# Sheet_1_2022-06-29.net
KiCad netlist of a schematic drawn in Altium Designer
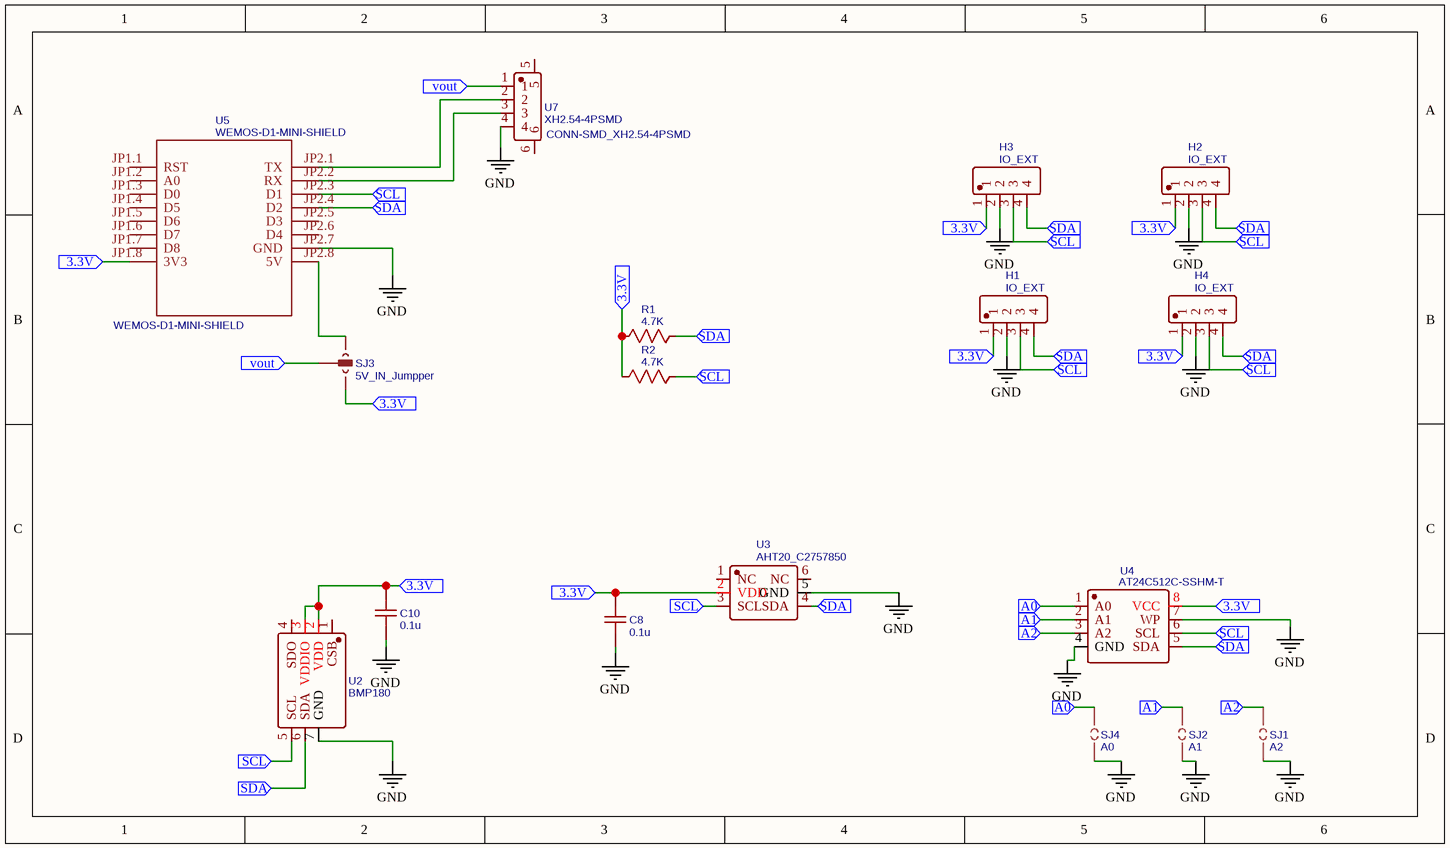
[diagram p0: Sheet_1_2022-06-29.schdoc]

(export (version "E")
  (design (tool "Eeschema 10.0.6"))
  (components
    (comp (ref "C8")
      (value "0.1u")
      (fields (field (name "CONTRIBUTOR") "LCEDA_Lib"))
      (libsource (lib "altium-import") (part "root_1_0.1u_"))
    )
    (comp (ref "C10")
      (value "0.1u")
      (fields (field (name "CONTRIBUTOR") "LCEDA_Lib"))
      (libsource (lib "altium-import") (part "root_1_0.1u_"))
    )
    (comp (ref "H1")
      (value "IO_EXT")
      (fields
        (field (name "BOM_SUPPLIER PART") "C706876")
        (field (name "BOM_MANUFACTURER PART") "X6511WV-04H-C30D60")
        (field (name "CONTRIBUTOR") "LCSC")
      )
      (libsource (lib "altium-import") (part "root_1_IO_EXT_"))
    )
    (comp (ref "H2")
      (value "IO_EXT")
      (fields
        (field (name "BOM_SUPPLIER PART") "C706876")
        (field (name "BOM_MANUFACTURER PART") "X6511WV-04H-C30D60")
        (field (name "CONTRIBUTOR") "LCSC")
      )
      (libsource (lib "altium-import") (part "root_1_IO_EXT_"))
    )
    (comp (ref "H3")
      (value "IO_EXT")
      (fields
        (field (name "BOM_SUPPLIER PART") "C706876")
        (field (name "BOM_MANUFACTURER PART") "X6511WV-04H-C30D60")
        (field (name "CONTRIBUTOR") "LCSC")
      )
      (libsource (lib "altium-import") (part "root_1_IO_EXT_"))
    )
    (comp (ref "H4")
      (value "IO_EXT")
      (fields
        (field (name "BOM_SUPPLIER PART") "C706876")
        (field (name "BOM_MANUFACTURER PART") "X6511WV-04H-C30D60")
        (field (name "CONTRIBUTOR") "LCSC")
      )
      (libsource (lib "altium-import") (part "root_1_IO_EXT_"))
    )
    (comp (ref "R1")
      (value "4.7K")
      (fields (field (name "CONTRIBUTOR") "LCEDA_Lib"))
      (libsource (lib "altium-import") (part "root_2_4.7K_"))
    )
    (comp (ref "R2")
      (value "4.7K")
      (fields (field (name "CONTRIBUTOR") "LCEDA_Lib"))
      (libsource (lib "altium-import") (part "root_2_4.7K_"))
    )
    (comp (ref "SJ1")
      (value "A2")
      (fields (field (name "CONTRIBUTOR") "torusww"))
      (libsource (lib "altium-import") (part "root_1_A2_"))
    )
    (comp (ref "SJ2")
      (value "A1")
      (fields (field (name "CONTRIBUTOR") "torusww"))
      (libsource (lib "altium-import") (part "root_1_A1_"))
    )
    (comp (ref "SJ3")
      (value "5V_IN_Jumpper")
      (fields (field (name "CONTRIBUTOR") "SparkFun"))
      (libsource (lib "altium-import") (part "root_0_5V_IN_Jumpper_"))
    )
    (comp (ref "SJ4")
      (value "A0")
      (fields (field (name "CONTRIBUTOR") "torusww"))
      (libsource (lib "altium-import") (part "root_1_A0_"))
    )
    (comp (ref "U2")
      (value "BMP180")
      (fields (field (name "BOM_SUPPLIER PART") "C438474") (field (name "CONTRIBUTOR") "LCSC"))
      (libsource (lib "altium-import") (part "root_3_BMP180_"))
    )
    (comp (ref "U3")
      (value "AHT20_C2757850")
      (fields
        (field (name "BOM_SUPPLIER PART") "C2757850")
        (field (name "BOM_MANUFACTURER PART") "AHT20")
        (field (name "CONTRIBUTOR") "LCSC")
      )
      (libsource (lib "altium-import") (part "root_0_AHT20_C2757850_"))
    )
    (comp (ref "U4")
      (value "AT24C512C-SSHM-T")
      (fields (field (name "BOM_SUPPLIER PART") "C54668"))
      (libsource (lib "altium-import") (part "root_0_AT24C512C-SSHM-T_"))
    )
    (comp (ref "U5")
      (value "WEMOS-D1-MINI-SHIELD")
      (description "Template for WEMOS D1 mini compatible shields")
      (libsource (lib "altium-import") (part "root_0_WEMOS-D1-MINI-SHIELD_"))
    )
    (comp (ref "U7")
      (value "XH2.54-4PSMD")
      (fields (field (name "BOM_SUPPLIER PART") "C9900001014") (field (name "CONTRIBUTOR") "LCSC"))
      (libsource (lib "altium-import") (part "root_0_XH2.54-4PSMD_"))
    )
  )
  (nets
    (net (code "1") (name "/3.3V") (class "Default")
      (node (ref "C10") (pin "2") (pinfunction "2_2") (pintype "passive"))
      (node (ref "C8") (pin "2") (pinfunction "2_2") (pintype "passive"))
      (node (ref "H1") (pin "1") (pinfunction "1_1") (pintype "passive"))
      (node (ref "H2") (pin "1") (pinfunction "1_1") (pintype "passive"))
      (node (ref "H3") (pin "1") (pinfunction "1_1") (pintype "passive"))
      (node (ref "H4") (pin "1") (pinfunction "1_1") (pintype "passive"))
      (node (ref "R1") (pin "2") (pinfunction "2_2") (pintype "passive"))
      (node (ref "R2") (pin "2") (pinfunction "2_2") (pintype "passive"))
      (node (ref "SJ3") (pin "3") (pinfunction "3_3") (pintype "passive"))
      (node (ref "U2") (pin "2") (pinfunction "VDD_2") (pintype "passive"))
      (node (ref "U2") (pin "3") (pinfunction "VDDIO_3") (pintype "passive"))
      (node (ref "U3") (pin "2") (pinfunction "VDD_2") (pintype "passive"))
      (node (ref "U4") (pin "8") (pinfunction "VCC_8") (pintype "passive"))
      (node (ref "U5") (pin "JP1.8") (pinfunction "3V3_JP1.8") (pintype "passive"))
    )
    (net (code "2") (name "/A0") (class "Default")
      (node (ref "SJ4") (pin "2") (pinfunction "2_2") (pintype "passive"))
      (node (ref "U4") (pin "1") (pinfunction "A0_1") (pintype "passive"))
    )
    (net (code "3") (name "/A1") (class "Default")
      (node (ref "SJ2") (pin "2") (pinfunction "2_2") (pintype "passive"))
      (node (ref "U4") (pin "2") (pinfunction "A1_2") (pintype "passive"))
    )
    (net (code "4") (name "/A2") (class "Default")
      (node (ref "SJ1") (pin "2") (pinfunction "2_2") (pintype "passive"))
      (node (ref "U4") (pin "3") (pinfunction "A2_3") (pintype "passive"))
    )
    (net (code "5") (name "/SCL") (class "Default")
      (node (ref "H1") (pin "3") (pinfunction "3_3") (pintype "passive"))
      (node (ref "H2") (pin "3") (pinfunction "3_3") (pintype "passive"))
      (node (ref "H3") (pin "3") (pinfunction "3_3") (pintype "passive"))
      (node (ref "H4") (pin "3") (pinfunction "3_3") (pintype "passive"))
      (node (ref "R2") (pin "1") (pinfunction "1_1") (pintype "passive"))
      (node (ref "U2") (pin "5") (pinfunction "SCL_5") (pintype "passive"))
      (node (ref "U3") (pin "3") (pinfunction "SCL_3") (pintype "passive"))
      (node (ref "U4") (pin "6") (pinfunction "SCL_6") (pintype "passive"))
      (node (ref "U5") (pin "JP2.3") (pinfunction "D1_JP2.3") (pintype "passive"))
    )
    (net (code "6") (name "/SDA") (class "Default")
      (node (ref "H1") (pin "4") (pinfunction "4_4") (pintype "passive"))
      (node (ref "H2") (pin "4") (pinfunction "4_4") (pintype "passive"))
      (node (ref "H3") (pin "4") (pinfunction "4_4") (pintype "passive"))
      (node (ref "H4") (pin "4") (pinfunction "4_4") (pintype "passive"))
      (node (ref "R1") (pin "1") (pinfunction "1_1") (pintype "passive"))
      (node (ref "U2") (pin "6") (pinfunction "SDA_6") (pintype "passive"))
      (node (ref "U3") (pin "4") (pinfunction "SDA_4") (pintype "passive"))
      (node (ref "U4") (pin "5") (pinfunction "SDA_5") (pintype "passive"))
      (node (ref "U5") (pin "JP2.4") (pinfunction "D2_JP2.4") (pintype "passive"))
    )
    (net (code "7") (name "/vout") (class "Default")
      (node (ref "SJ3") (pin "2") (pinfunction "2_2") (pintype "passive"))
      (node (ref "U7") (pin "1") (pinfunction "1_1") (pintype "passive"))
    )
    (net (code "8") (name "GND") (class "Default")
      (node (ref "C10") (pin "1") (pinfunction "1_1") (pintype "passive"))
      (node (ref "C8") (pin "1") (pinfunction "1_1") (pintype "passive"))
      (node (ref "H1") (pin "2") (pinfunction "2_2") (pintype "passive"))
      (node (ref "H2") (pin "2") (pinfunction "2_2") (pintype "passive"))
      (node (ref "H3") (pin "2") (pinfunction "2_2") (pintype "passive"))
      (node (ref "H4") (pin "2") (pinfunction "2_2") (pintype "passive"))
      (node (ref "SJ1") (pin "1") (pinfunction "1_1") (pintype "passive"))
      (node (ref "SJ2") (pin "1") (pinfunction "1_1") (pintype "passive"))
      (node (ref "SJ4") (pin "1") (pinfunction "1_1") (pintype "passive"))
      (node (ref "U2") (pin "7") (pinfunction "GND_7") (pintype "passive"))
      (node (ref "U3") (pin "5") (pinfunction "GND_5") (pintype "passive"))
      (node (ref "U4") (pin "4") (pinfunction "GND_4") (pintype "passive"))
      (node (ref "U4") (pin "7") (pinfunction "WP_7") (pintype "passive"))
      (node (ref "U5") (pin "JP2.7") (pinfunction "GND_JP2.7") (pintype "passive"))
      (node (ref "U7") (pin "4") (pinfunction "4_4") (pintype "passive"))
    )
    (net (code "9") (name "Net-(U5-5V)") (class "Default")
      (node (ref "SJ3") (pin "1") (pinfunction "1_1") (pintype "passive"))
      (node (ref "U5") (pin "JP2.8") (pinfunction "5V_JP2.8") (pintype "passive"))
    )
    (net (code "10") (name "Net-(U5-RX)") (class "Default")
      (node (ref "U5") (pin "JP2.2") (pinfunction "RX_JP2.2") (pintype "passive"))
      (node (ref "U7") (pin "3") (pinfunction "3_3") (pintype "passive"))
    )
    (net (code "11") (name "Net-(U5-TX)") (class "Default")
      (node (ref "U5") (pin "JP2.1") (pinfunction "TX_JP2.1") (pintype "passive"))
      (node (ref "U7") (pin "2") (pinfunction "2_2") (pintype "passive"))
    )
    (net (code "12") (name "unconnected-(U2-CSB-Pad1)") (class "Default")
      (node (ref "U2") (pin "1") (pinfunction "CSB_1") (pintype "passive"))
    )
    (net (code "13") (name "unconnected-(U2-SDO-Pad4)") (class "Default")
      (node (ref "U2") (pin "4") (pinfunction "SDO_4") (pintype "passive"))
    )
    (net (code "14") (name "unconnected-(U3-NC-Pad1)") (class "Default")
      (node (ref "U3") (pin "1") (pinfunction "NC_1") (pintype "passive"))
    )
    (net (code "15") (name "unconnected-(U3-NC-Pad6)") (class "Default")
      (node (ref "U3") (pin "6") (pinfunction "NC_6") (pintype "passive"))
    )
    (net (code "16") (name "unconnected-(U5-A0-PadJP1.2)") (class "Default")
      (node (ref "U5") (pin "JP1.2") (pinfunction "A0_JP1.2") (pintype "passive"))
    )
    (net (code "17") (name "unconnected-(U5-D0-PadJP1.3)") (class "Default")
      (node (ref "U5") (pin "JP1.3") (pinfunction "D0_JP1.3") (pintype "passive"))
    )
    (net (code "18") (name "unconnected-(U5-D3-PadJP2.5)") (class "Default")
      (node (ref "U5") (pin "JP2.5") (pinfunction "D3_JP2.5") (pintype "passive"))
    )
    (net (code "19") (name "unconnected-(U5-D4-PadJP2.6)") (class "Default")
      (node (ref "U5") (pin "JP2.6") (pinfunction "D4_JP2.6") (pintype "passive"))
    )
    (net (code "20") (name "unconnected-(U5-D5-PadJP1.4)") (class "Default")
      (node (ref "U5") (pin "JP1.4") (pinfunction "D5_JP1.4") (pintype "passive"))
    )
    (net (code "21") (name "unconnected-(U5-D6-PadJP1.5)") (class "Default")
      (node (ref "U5") (pin "JP1.5") (pinfunction "D6_JP1.5") (pintype "passive"))
    )
    (net (code "22") (name "unconnected-(U5-D7-PadJP1.6)") (class "Default")
      (node (ref "U5") (pin "JP1.6") (pinfunction "D7_JP1.6") (pintype "passive"))
    )
    (net (code "23") (name "unconnected-(U5-D8-PadJP1.7)") (class "Default")
      (node (ref "U5") (pin "JP1.7") (pinfunction "D8_JP1.7") (pintype "passive"))
    )
    (net (code "24") (name "unconnected-(U5-RST-PadJP1.1)") (class "Default")
      (node (ref "U5") (pin "JP1.1") (pinfunction "RST_JP1.1") (pintype "passive"))
    )
    (net (code "25") (name "unconnected-(U7-Pad5)") (class "Default")
      (node (ref "U7") (pin "5") (pinfunction "5_5") (pintype "passive"))
    )
    (net (code "26") (name "unconnected-(U7-Pad6)") (class "Default")
      (node (ref "U7") (pin "6") (pinfunction "6_6") (pintype "passive"))
    )
  )
)
